# Luna_Board_Sheet.net
KiCad netlist of a schematic drawn in Altium Designer
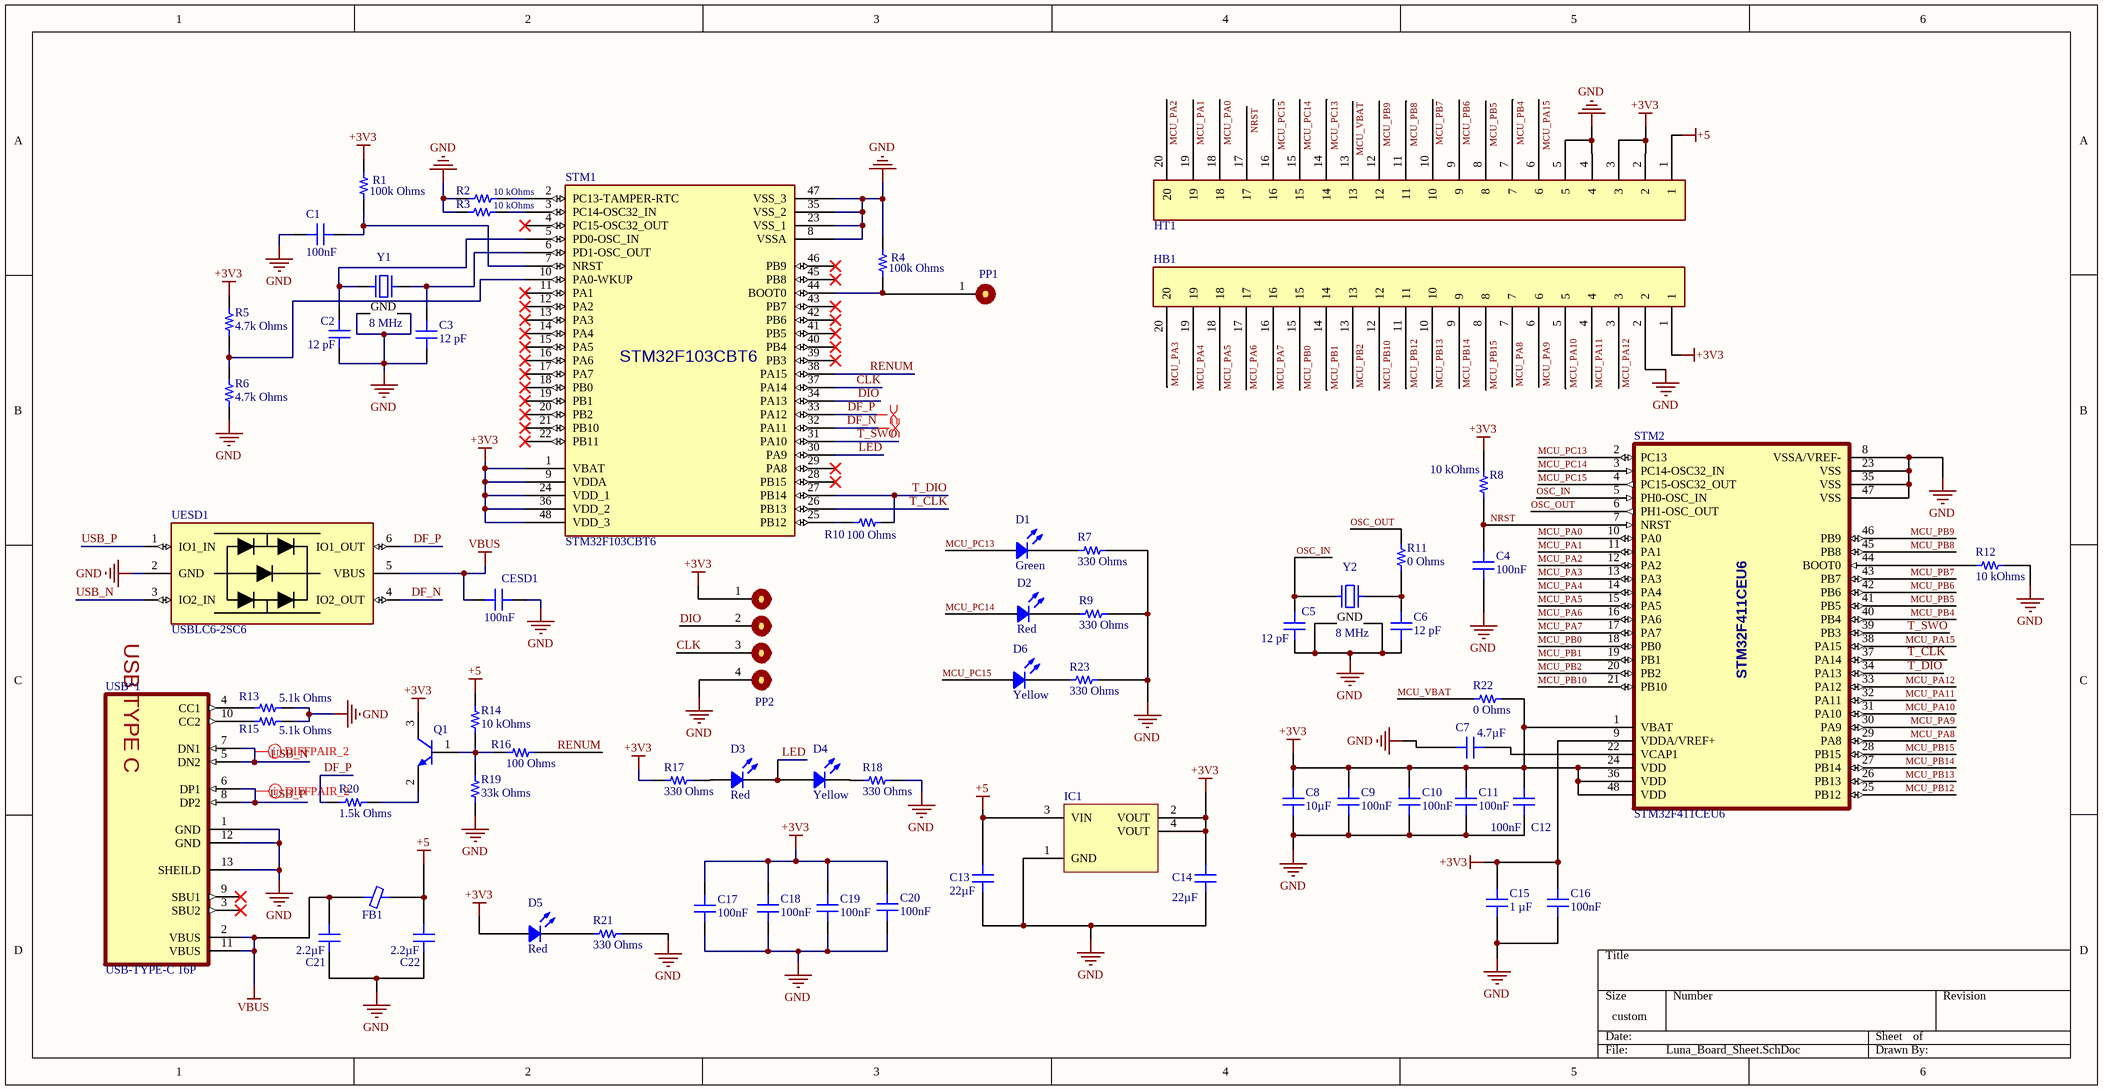
[diagram p0: Luna_Board_Sheet.SchDoc]

(export (version "E")
  (design (tool "Eeschema 10.0.6"))
  (components
    (comp (ref "C1")
      (value "100nF")
      (footprint "CAP 0603_1608")
      (description "CAP CER 0.1UF 100V X7R 0603")
      (fields
        (field (name "PART NUMBER") "06031C104KAT2A")
        (field (name "CAPACITANCE") "100nF")
        (field (name "MANUFACTURER") "AVX Corporation")
      )
      (libsource (lib "Celestial Altium Library - altium_library") (part "Capacitor"))
    )
    (comp (ref "C2")
      (value "12 pF")
      (footprint "CAP 0603_1608")
      (description "HIGH-Q MLCC (CF): 0603, 22 PF (1")
      (fields
        (field (name "PART NUMBER") "C06CF220F-9ZN-X0T")
        (field (name "CAPACITANCE") "12 pF")
        (field (name "MANUFACTURER") "Knowles Dielectric Labs")
      )
      (libsource (lib "Celestial Altium Library - altium_library") (part "Capacitor"))
    )
    (comp (ref "C3")
      (value "12 pF")
      (footprint "CAP 0603_1608")
      (description "HIGH-Q MLCC (CF): 0603, 22 PF (1")
      (fields
        (field (name "PART NUMBER") "C06CF220F-9ZN-X0T")
        (field (name "CAPACITANCE") "12 pF")
        (field (name "MANUFACTURER") "Knowles Dielectric Labs")
      )
      (libsource (lib "Celestial Altium Library - altium_library") (part "Capacitor"))
    )
    (comp (ref "C4")
      (value "100nF")
      (footprint "CAP 0603_1608")
      (description "CAP CER 0.1UF 100V X7R 0603")
      (fields
        (field (name "PART NUMBER") "06031C104KAT2A")
        (field (name "CAPACITANCE") "100nF")
        (field (name "MANUFACTURER") "AVX Corporation")
      )
      (libsource (lib "Celestial Altium Library - altium_library") (part "Capacitor"))
    )
    (comp (ref "C5")
      (value "12 pF")
      (footprint "CAP 0603_1608")
      (description "HIGH-Q MLCC (CF): 0603, 22 PF (1")
      (fields
        (field (name "PART NUMBER") "C06CF220F-9ZN-X0T")
        (field (name "CAPACITANCE") "12 pF")
        (field (name "MANUFACTURER") "Knowles Dielectric Labs")
      )
      (libsource (lib "Celestial Altium Library - altium_library") (part "Capacitor"))
    )
    (comp (ref "C6")
      (value "12 pF")
      (footprint "CAP 0603_1608")
      (description "HIGH-Q MLCC (CF): 0603, 22 PF (1")
      (fields
        (field (name "PART NUMBER") "C06CF220F-9ZN-X0T")
        (field (name "CAPACITANCE") "12 pF")
        (field (name "MANUFACTURER") "Knowles Dielectric Labs")
      )
      (libsource (lib "Celestial Altium Library - altium_library") (part "Capacitor"))
    )
    (comp (ref "C7")
      (value "4.7µF")
      (footprint "CAP 0603_1608")
      (description "CAP CER 4.7UF 10V Y5V 0603")
      (fields
        (field (name "PART NUMBER") "0603ZG475ZAT2A")
        (field (name "CAPACITANCE") "4.7µF")
        (field (name "MANUFACTURER") "AVX Corporation")
      )
      (libsource (lib "Celestial Altium Library - altium_library") (part "Capacitor"))
    )
    (comp (ref "C8")
      (value "10µF")
      (footprint "CAP 0603_1608")
      (description "CAP CER 10UF 10V X5R 0603")
      (fields
        (field (name "PART NUMBER") "0603ZD106KAT2A")
        (field (name "CAPACITANCE") "10µF")
        (field (name "MANUFACTURER") "AVX Corporation")
      )
      (libsource (lib "Celestial Altium Library - altium_library") (part "Capacitor"))
    )
    (comp (ref "C9")
      (value "100nF")
      (footprint "CAP 0603_1608")
      (description "CAP CER 0.1UF 100V X7R 0603")
      (fields
        (field (name "PART NUMBER") "06031C104KAT2A")
        (field (name "CAPACITANCE") "100nF")
        (field (name "MANUFACTURER") "AVX Corporation")
      )
      (libsource (lib "Celestial Altium Library - altium_library") (part "Capacitor"))
    )
    (comp (ref "C10")
      (value "100nF")
      (footprint "CAP 0603_1608")
      (description "CAP CER 0.1UF 100V X7R 0603")
      (fields
        (field (name "PART NUMBER") "06031C104KAT2A")
        (field (name "CAPACITANCE") "100nF")
        (field (name "MANUFACTURER") "AVX Corporation")
      )
      (libsource (lib "Celestial Altium Library - altium_library") (part "Capacitor"))
    )
    (comp (ref "C11")
      (value "100nF")
      (footprint "CAP 0603_1608")
      (description "CAP CER 0.1UF 100V X7R 0603")
      (fields
        (field (name "PART NUMBER") "06031C104KAT2A")
        (field (name "CAPACITANCE") "100nF")
        (field (name "MANUFACTURER") "AVX Corporation")
      )
      (libsource (lib "Celestial Altium Library - altium_library") (part "Capacitor"))
    )
    (comp (ref "C12")
      (value "100nF")
      (footprint "CAP 0603_1608")
      (description "CAP CER 0.1UF 100V X7R 0603")
      (fields
        (field (name "PART NUMBER") "06031C104KAT2A")
        (field (name "CAPACITANCE") "100nF")
        (field (name "MANUFACTURER") "AVX Corporation")
      )
      (libsource (lib "Celestial Altium Library - altium_library") (part "Capacitor"))
    )
    (comp (ref "C13")
      (value "22µF")
      (footprint "CAP 0805_2012")
      (description "CAP CER 22UF 10V X5R 0805")
      (fields
        (field (name "PART NUMBER") "0805ZD226MAT2A")
        (field (name "CAPACITANCE") "22µF")
        (field (name "MANUFACTURER") "AVX Corporation")
      )
      (libsource (lib "Celestial Altium Library - altium_library") (part "Capacitor"))
    )
    (comp (ref "C14")
      (value "22µF")
      (footprint "CAP 0805_2012")
      (description "CAP CER 22UF 10V X5R 0805")
      (fields
        (field (name "PART NUMBER") "0805ZD226MAT2A")
        (field (name "CAPACITANCE") "22µF")
        (field (name "MANUFACTURER") "AVX Corporation")
      )
      (libsource (lib "Celestial Altium Library - altium_library") (part "Capacitor"))
    )
    (comp (ref "C15")
      (value "1 µF")
      (footprint "CAP 0603_1608")
      (description "CAP SMT06031F16VDC")
      (fields
        (field (name "PART NUMBER") "NMC0603X7R105K16TRPF")
        (field (name "CAPACITANCE") "1 µF")
        (field (name "MANUFACTURER") "NIC Components Corp")
      )
      (libsource (lib "Celestial Altium Library - altium_library") (part "Capacitor"))
    )
    (comp (ref "C16")
      (value "100nF")
      (footprint "CAP 0603_1608")
      (description "CAP CER 0.1UF 100V X7R 0603")
      (fields
        (field (name "PART NUMBER") "06031C104KAT2A")
        (field (name "CAPACITANCE") "100nF")
        (field (name "MANUFACTURER") "AVX Corporation")
      )
      (libsource (lib "Celestial Altium Library - altium_library") (part "Capacitor"))
    )
    (comp (ref "C17")
      (value "100nF")
      (footprint "CAP 0603_1608")
      (description "CAP CER 0.1UF 100V X7R 0603")
      (fields
        (field (name "PART NUMBER") "06031C104KAT2A")
        (field (name "CAPACITANCE") "100nF")
        (field (name "MANUFACTURER") "AVX Corporation")
      )
      (libsource (lib "Celestial Altium Library - altium_library") (part "Capacitor"))
    )
    (comp (ref "C18")
      (value "100nF")
      (footprint "CAP 0603_1608")
      (description "CAP CER 0.1UF 100V X7R 0603")
      (fields
        (field (name "PART NUMBER") "06031C104KAT2A")
        (field (name "CAPACITANCE") "100nF")
        (field (name "MANUFACTURER") "AVX Corporation")
      )
      (libsource (lib "Celestial Altium Library - altium_library") (part "Capacitor"))
    )
    (comp (ref "C19")
      (value "100nF")
      (footprint "CAP 0603_1608")
      (description "CAP CER 0.1UF 100V X7R 0603")
      (fields
        (field (name "PART NUMBER") "06031C104KAT2A")
        (field (name "CAPACITANCE") "100nF")
        (field (name "MANUFACTURER") "AVX Corporation")
      )
      (libsource (lib "Celestial Altium Library - altium_library") (part "Capacitor"))
    )
    (comp (ref "C20")
      (value "100nF")
      (footprint "CAP 0603_1608")
      (description "CAP CER 0.1UF 100V X7R 0603")
      (fields
        (field (name "PART NUMBER") "06031C104KAT2A")
        (field (name "CAPACITANCE") "100nF")
        (field (name "MANUFACTURER") "AVX Corporation")
      )
      (libsource (lib "Celestial Altium Library - altium_library") (part "Capacitor"))
    )
    (comp (ref "C21")
      (value "2.2µF")
      (footprint "CAP 0603_1608")
      (description "CAP CER 0.1UF 100V X7R 0603")
      (fields
        (field (name "PART NUMBER") "06031C104KAT2A")
        (field (name "CAPACITANCE") "2.2µF")
        (field (name "MANUFACTURER") "AVX Corporation")
      )
      (libsource (lib "Celestial Altium Library - altium_library") (part "Capacitor"))
    )
    (comp (ref "C22")
      (value "2.2µF")
      (footprint "CAP 0603_1608")
      (description "CAP CER 0.1UF 100V X7R 0603")
      (fields
        (field (name "PART NUMBER") "06031C104KAT2A")
        (field (name "CAPACITANCE") "2.2µF")
        (field (name "MANUFACTURER") "AVX Corporation")
      )
      (libsource (lib "Celestial Altium Library - altium_library") (part "Capacitor"))
    )
    (comp (ref "CESD1")
      (value "100nF")
      (footprint "CAP 0603_1608")
      (description "CAP CER 0.1UF 100V X7R 0603")
      (fields
        (field (name "PART NUMBER") "06031C104KAT2A")
        (field (name "CAPACITANCE") "100nF")
        (field (name "MANUFACTURER") "AVX Corporation")
      )
      (libsource (lib "Celestial Altium Library - altium_library") (part "Capacitor"))
    )
    (comp (ref "D1")
      (value "Green")
      (footprint "LED 0805_2012 GREEN")
      (description "0805 LED RED 570NM DOMINANT, 565")
      (fields
        (field (name "PART NUMBER") "QBLP631-YG1-2943")
        (field (name "MANUFACTURER") "QT Brightek (QTB)")
      )
      (libsource (lib "Celestial Altium Library - altium_library") (part "LED"))
    )
    (comp (ref "D2")
      (value "Red")
      (footprint "LED 0805_2012 RED")
      (description "0805 LED RED 640NM DOMINANT, 660")
      (fields (field (name "PART NUMBER") "QBLP631-S3") (field (name "MANUFACTURER") "QT Brightek (QTB)"))
      (libsource (lib "Celestial Altium Library - altium_library") (part "LED"))
    )
    (comp (ref "D3")
      (value "Red")
      (footprint "LED 0805_2012 RED")
      (description "0805 LED RED 640NM DOMINANT, 660")
      (fields (field (name "PART NUMBER") "QBLP631-S3") (field (name "MANUFACTURER") "QT Brightek (QTB)"))
      (libsource (lib "Celestial Altium Library - altium_library") (part "LED"))
    )
    (comp (ref "D4")
      (value "Yellow")
      (footprint "LED 0805_2012 YELLOW")
      (description "LED YELLOW DIFFUSED 0805 SMD")
      (fields (field (name "PART NUMBER") "597-3222-407NF") (field (name "MANUFACTURER") "Dialight"))
      (libsource (lib "Celestial Altium Library - altium_library") (part "LED"))
    )
    (comp (ref "D5")
      (value "Red")
      (footprint "LED 0805_2012 RED")
      (description "0805 LED RED 640NM DOMINANT, 660")
      (fields (field (name "PART NUMBER") "QBLP631-S3") (field (name "MANUFACTURER") "QT Brightek (QTB)"))
      (libsource (lib "Celestial Altium Library - altium_library") (part "LED"))
    )
    (comp (ref "D6")
      (value "Yellow")
      (footprint "LED 0805_2012 YELLOW")
      (description "LED YELLOW DIFFUSED 0805 SMD")
      (fields (field (name "PART NUMBER") "597-3222-407NF") (field (name "MANUFACTURER") "Dialight"))
      (libsource (lib "Celestial Altium Library - altium_library") (part "LED"))
    )
    (comp (ref "FB1")
      (value "Ferrite Bead")
      (footprint "FER 0603_1608")
      (description "FERRITEBEAD SMD Z100MHZ=600OHM 7")
      (fields
        (field (name "PART NUMBER") "BLM18DN601SZ1D")
        (field (name "MANUFACTURER") "Murata Electronics")
      )
      (libsource (lib "Celestial Altium Library - altium_library") (part "Ferrite Chip"))
    )
    (comp (ref "HB1")
      (value "2.54mm_TH_1x20_pin_header")
      (footprint "2.54mm_TH_1x20_pin_header")
      (libsource (lib "ARAF_PERSONAL_INTEGRATED_LIBRARY") (part "2.54mm_TH_1x20_pin_header"))
    )
    (comp (ref "HT1")
      (value "2.54mm_TH_1x20_pin_header")
      (footprint "2.54mm_TH_1x20_pin_header")
      (libsource (lib "") (part "2.54mm_TH_1x20_pin_header_1"))
    )
    (comp (ref "IC1")
      (value "AMS1117-3.3")
      (footprint "ST SOT-223")
      (description "IC REG LINEAR 3.3V 1.2A SOT223")
      (fields (field (name "PART NUMBER") "LDL1117S33R") (field (name "MANUFACTURER") "STMicroelectronics"))
      (libsource (lib "Celestial Altium Library - altium_library") (part "ST LDL1117"))
    )
    (comp (ref "PP1")
      (value "pin_pad_1")
      (footprint "pinpad_1")
      (libsource (lib "ARAF_PERSONAL_INTEGRATED_LIBRARY") (part "pin_pad_1"))
    )
    (comp (ref "PP2")
      (value "pin_pad_4")
      (footprint "pinpad_4")
      (libsource (lib "ARAF_PERSONAL_INTEGRATED_LIBRARY") (part "pin_pad_4"))
    )
    (comp (ref "Q1")
      (value "500mA NPN BJT")
      (footprint "DIODES SOT-23-3")
      (description "TRANS NPN 60V 1A SOT23-3")
      (fields (field (name "PART NUMBER") "DNLS160-7") (field (name "MANUFACTURER") "Diodes Incorporated"))
      (libsource (lib "Celestial Altium Library - altium_library") (part "DIODES INC NPN SOT-23-3"))
    )
    (comp (ref "R1")
      (value "100k Ohms")
      (footprint "RES 0603_1608")
      (description "RES 100K OHM 0.1% 1/16W 0603")
      (fields
        (field (name "PART NUMBER") "RNCS0603BKE10K0")
        (field (name "MANUFACTURER") "Stackpole Electronics Inc")
      )
      (libsource (lib "Celestial Altium Library - altium_library") (part "Resistor"))
    )
    (comp (ref "R2")
      (value "10 kOhms")
      (footprint "RES 0603_1608")
      (description "RES 10K OHM 0.1% 1/16W 0603")
      (fields
        (field (name "PART NUMBER") "RNCS0603BKE10K0")
        (field (name "MANUFACTURER") "Stackpole Electronics Inc")
      )
      (libsource (lib "Celestial Altium Library - altium_library") (part "Resistor"))
    )
    (comp (ref "R3")
      (value "10 kOhms")
      (footprint "RES 0603_1608")
      (description "RES 10K OHM 0.1% 1/16W 0603")
      (fields
        (field (name "PART NUMBER") "RNCS0603BKE10K0")
        (field (name "MANUFACTURER") "Stackpole Electronics Inc")
      )
      (libsource (lib "Celestial Altium Library - altium_library") (part "Resistor"))
    )
    (comp (ref "R4")
      (value "100k Ohms")
      (footprint "RES 0603_1608")
      (description "RES 100K OHM 0.1% 1/16W 0603")
      (fields
        (field (name "PART NUMBER") "RNCS0603BKE10K0")
        (field (name "MANUFACTURER") "Stackpole Electronics Inc")
      )
      (libsource (lib "Celestial Altium Library - altium_library") (part "Resistor"))
    )
    (comp (ref "R5")
      (value "4.7k Ohms")
      (footprint "RES 0603_1608")
      (description "RES 4.7K OHM 0.1% 1/16W 0603")
      (fields
        (field (name "PART NUMBER") "RNCS0603BKE10K0")
        (field (name "MANUFACTURER") "Stackpole Electronics Inc")
      )
      (libsource (lib "Celestial Altium Library - altium_library") (part "Resistor"))
    )
    (comp (ref "R6")
      (value "4.7k Ohms")
      (footprint "RES 0603_1608")
      (description "RES 4.7k OHM 0.1% 1/16W 0603")
      (fields
        (field (name "PART NUMBER") "RNCS0603BKE10K0")
        (field (name "MANUFACTURER") "Stackpole Electronics Inc")
      )
      (libsource (lib "Celestial Altium Library - altium_library") (part "Resistor"))
    )
    (comp (ref "R7")
      (value "330 Ohms")
      (footprint "RES 0603_1608")
      (description "RES 10K OHM 0.1% 1/16W 0603")
      (fields
        (field (name "PART NUMBER") "RNCS0603BKE10K0")
        (field (name "MANUFACTURER") "Stackpole Electronics Inc")
      )
      (libsource (lib "Celestial Altium Library - altium_library") (part "Resistor"))
    )
    (comp (ref "R8")
      (value "10 kOhms")
      (footprint "RES 0603_1608")
      (description "RES 10K OHM 0.1% 1/16W 0603")
      (fields
        (field (name "PART NUMBER") "RNCS0603BKE10K0")
        (field (name "MANUFACTURER") "Stackpole Electronics Inc")
      )
      (libsource (lib "Celestial Altium Library - altium_library") (part "Resistor"))
    )
    (comp (ref "R9")
      (value "330 Ohms")
      (footprint "RES 0603_1608")
      (description "RES 10K OHM 0.1% 1/16W 0603")
      (fields
        (field (name "PART NUMBER") "RNCS0603BKE10K0")
        (field (name "MANUFACTURER") "Stackpole Electronics Inc")
      )
      (libsource (lib "Celestial Altium Library - altium_library") (part "Resistor"))
    )
    (comp (ref "R10")
      (value "100 Ohms")
      (footprint "RES 0603_1608")
      (description "RES 100 OHM 0.1% 1/16W 0603")
      (fields
        (field (name "PART NUMBER") "RNCS0603BKE10K0")
        (field (name "MANUFACTURER") "Stackpole Electronics Inc")
      )
      (libsource (lib "Celestial Altium Library - altium_library") (part "Resistor"))
    )
    (comp (ref "R11")
      (value "0 Ohms")
      (footprint "RES 0603_1608")
      (description "RES 0 OHM JUMPER 0603")
      (fields
        (field (name "PART NUMBER") "TLRZ1JTTD")
        (field (name "MANUFACTURER") "KOA Speer Electronics, Inc.")
      )
      (libsource (lib "Celestial Altium Library - altium_library") (part "Resistor"))
    )
    (comp (ref "R12")
      (value "10 kOhms")
      (footprint "RES 0603_1608")
      (description "RES 10K OHM 0.1% 1/16W 0603")
      (fields
        (field (name "PART NUMBER") "RNCS0603BKE10K0")
        (field (name "MANUFACTURER") "Stackpole Electronics Inc")
      )
      (libsource (lib "Celestial Altium Library - altium_library") (part "Resistor"))
    )
    (comp (ref "R13")
      (value "5.1k Ohms")
      (footprint "RES 0603_1608")
      (description "RES 10K OHM 0.1% 1/16W 0603")
      (fields
        (field (name "PART NUMBER") "RNCS0603BKE10K0")
        (field (name "MANUFACTURER") "Stackpole Electronics Inc")
      )
      (libsource (lib "Celestial Altium Library - altium_library") (part "Resistor"))
    )
    (comp (ref "R14")
      (value "10 kOhms")
      (footprint "RES 0603_1608")
      (description "RES 10K OHM 0.1% 1/16W 0603")
      (fields
        (field (name "PART NUMBER") "RNCS0603BKE10K0")
        (field (name "MANUFACTURER") "Stackpole Electronics Inc")
      )
      (libsource (lib "Celestial Altium Library - altium_library") (part "Resistor"))
    )
    (comp (ref "R15")
      (value "5.1k Ohms")
      (footprint "RES 0603_1608")
      (description "RES 10K OHM 0.1% 1/16W 0603")
      (fields
        (field (name "PART NUMBER") "RNCS0603BKE10K0")
        (field (name "MANUFACTURER") "Stackpole Electronics Inc")
      )
      (libsource (lib "Celestial Altium Library - altium_library") (part "Resistor"))
    )
    (comp (ref "R16")
      (value "100 Ohms")
      (footprint "RES 0603_1608")
      (description "RES 10K OHM 0.1% 1/16W 0603")
      (fields
        (field (name "PART NUMBER") "RNCS0603BKE10K0")
        (field (name "MANUFACTURER") "Stackpole Electronics Inc")
      )
      (libsource (lib "Celestial Altium Library - altium_library") (part "Resistor"))
    )
    (comp (ref "R17")
      (value "330 Ohms")
      (footprint "RES 0603_1608")
      (description "RES 10K OHM 0.1% 1/16W 0603")
      (fields
        (field (name "PART NUMBER") "RNCS0603BKE10K0")
        (field (name "MANUFACTURER") "Stackpole Electronics Inc")
      )
      (libsource (lib "Celestial Altium Library - altium_library") (part "Resistor"))
    )
    (comp (ref "R18")
      (value "330 Ohms")
      (footprint "RES 0603_1608")
      (description "RES 10K OHM 0.1% 1/16W 0603")
      (fields
        (field (name "PART NUMBER") "RNCS0603BKE10K0")
        (field (name "MANUFACTURER") "Stackpole Electronics Inc")
      )
      (libsource (lib "Celestial Altium Library - altium_library") (part "Resistor"))
    )
    (comp (ref "R19")
      (value "33k Ohms")
      (footprint "RES 0603_1608")
      (description "RES 10K OHM 0.1% 1/16W 0603")
      (fields
        (field (name "PART NUMBER") "RNCS0603BKE10K0")
        (field (name "MANUFACTURER") "Stackpole Electronics Inc")
      )
      (libsource (lib "Celestial Altium Library - altium_library") (part "Resistor"))
    )
    (comp (ref "R20")
      (value "1.5k Ohms")
      (footprint "RES 0603_1608")
      (description "RES 10K OHM 0.1% 1/16W 0603")
      (fields
        (field (name "PART NUMBER") "RNCS0603BKE10K0")
        (field (name "MANUFACTURER") "Stackpole Electronics Inc")
      )
      (libsource (lib "Celestial Altium Library - altium_library") (part "Resistor"))
    )
    (comp (ref "R21")
      (value "330 Ohms")
      (footprint "RES 0603_1608")
      (description "RES 10K OHM 0.1% 1/16W 0603")
      (fields
        (field (name "PART NUMBER") "RNCS0603BKE10K0")
        (field (name "MANUFACTURER") "Stackpole Electronics Inc")
      )
      (libsource (lib "Celestial Altium Library - altium_library") (part "Resistor"))
    )
    (comp (ref "R22")
      (value "0 Ohms")
      (footprint "RES 0603_1608")
      (description "RES 0 OHM JUMPER 0603")
      (fields
        (field (name "PART NUMBER") "TLRZ1JTTD")
        (field (name "MANUFACTURER") "KOA Speer Electronics, Inc.")
      )
      (libsource (lib "Celestial Altium Library - altium_library") (part "Resistor"))
    )
    (comp (ref "R23")
      (value "330 Ohms")
      (footprint "RES 0603_1608")
      (description "RES 10K OHM 0.1% 1/16W 0603")
      (fields
        (field (name "PART NUMBER") "RNCS0603BKE10K0")
        (field (name "MANUFACTURER") "Stackpole Electronics Inc")
      )
      (libsource (lib "Celestial Altium Library - altium_library") (part "Resistor"))
    )
    (comp (ref "STM1")
      (value "STM32F103CBT6")
      (footprint "STM32F103CBT6_FOOTPRINT")
      (description "128KB 2V~3.6V ARM-M3 20KB 72MHz FLASH 37 LQFP-48(7x7) Microcontrollers (MCU/MPU/SOC) ROHS")
      (fields (field (name "JLCPCB PART #") "C8304"))
      (libsource (lib "ARAF_PERSONAL_INTEGRATED_LIBRARY") (part "STM32F103CBT6"))
    )
    (comp (ref "STM2")
      (value "STM32F411CEU6")
      (footprint "STM32F411CEU6_Footprint")
      (libsource (lib "STM32F_Series_SCH_Library_ARAF") (part "STM32F411CEU6"))
    )
    (comp (ref "UESD1")
      (value "USBLC6-2SC6")
      (footprint "USBLC6-2SC6_Footprint")
      (fields (field (name "JLCPCB PART #") "C7519"))
      (libsource (lib "ESD_Protection_Components_Series_SCH_Library_ARAF") (part "USBLC6-2"))
    )
    (comp (ref "USB*1")
      (value "USB-TYPE-C 16P")
      (footprint "USB TYPE-C 24P SMD")
      (fields (field (name "LCSC PART") "C2765186"))
      (libsource (lib "USB_Connector_Series_SCH_Library_ARAF") (part "USB TYPE-C 24P SMD"))
    )
    (comp (ref "Y1")
      (value "8 MHz")
      (footprint "EPSON TSX-3225")
      (fields (field (name "PART NUMBER") "TSX-3225 16.0000MF10U-B0") (field (name "MANUFACTURER") "EPSON"))
      (libsource (lib "Celestial Altium Library - altium_library") (part "Epson Crystal TSX-3225"))
    )
    (comp (ref "Y2")
      (value "8 MHz")
      (footprint "EPSON TSX-3225")
      (description "CRYSTAL 16.0000MHZ 16PF SMD")
      (fields (field (name "PART NUMBER") "TSX-3225 16.0000MF10U-B0") (field (name "MANUFACTURER") "EPSON"))
      (libsource (lib "Celestial Altium Library - altium_library") (part "Epson Crystal TSX-3225"))
    )
  )
  (nets
    (net (code "1") (name "+3V3") (class "Default")
      (node (ref "C10") (pin "2") (pinfunction "2_2") (pintype "passive"))
      (node (ref "C11") (pin "2") (pinfunction "2_2") (pintype "passive"))
      (node (ref "C12") (pin "2") (pinfunction "2_2") (pintype "passive"))
      (node (ref "C14") (pin "2") (pinfunction "2_2") (pintype "passive"))
      (node (ref "C15") (pin "2") (pinfunction "2_2") (pintype "passive"))
      (node (ref "C16") (pin "2") (pinfunction "2_2") (pintype "passive"))
      (node (ref "C17") (pin "2") (pinfunction "2_2") (pintype "passive"))
      (node (ref "C18") (pin "2") (pinfunction "2_2") (pintype "passive"))
      (node (ref "C19") (pin "2") (pinfunction "2_2") (pintype "passive"))
      (node (ref "C20") (pin "2") (pinfunction "2_2") (pintype "passive"))
      (node (ref "C8") (pin "2") (pinfunction "2_2") (pintype "passive"))
      (node (ref "C9") (pin "2") (pinfunction "2_2") (pintype "passive"))
      (node (ref "D5") (pin "1") (pinfunction "1_1") (pintype "passive"))
      (node (ref "HB1") (pin "1") (pinfunction "1_1") (pintype "passive"))
      (node (ref "HT1") (pin "2") (pinfunction "2_2") (pintype "passive"))
      (node (ref "HT1") (pin "3") (pinfunction "3_3") (pintype "passive"))
      (node (ref "IC1") (pin "2") (pinfunction "VOUT_2") (pintype "passive"))
      (node (ref "IC1") (pin "4") (pinfunction "VOUT_4") (pintype "passive"))
      (node (ref "PP2") (pin "1") (pinfunction "1_1") (pintype "passive"))
      (node (ref "Q1") (pin "3") (pinfunction "C_3") (pintype "passive"))
      (node (ref "R1") (pin "1") (pinfunction "1_1") (pintype "passive"))
      (node (ref "R17") (pin "1") (pinfunction "1_1") (pintype "passive"))
      (node (ref "R22") (pin "1") (pinfunction "1_1") (pintype "passive"))
      (node (ref "R5") (pin "2") (pinfunction "2_2") (pintype "passive"))
      (node (ref "R8") (pin "1") (pinfunction "1_1") (pintype "passive"))
      (node (ref "STM1") (pin "1") (pinfunction "VBAT_1") (pintype "power_in"))
      (node (ref "STM1") (pin "24") (pinfunction "VDD_1_24") (pintype "power_in"))
      (node (ref "STM1") (pin "36") (pinfunction "VDD_2_36") (pintype "power_in"))
      (node (ref "STM1") (pin "48") (pinfunction "VDD_3_48") (pintype "power_in"))
      (node (ref "STM1") (pin "9") (pinfunction "VDDA_9") (pintype "power_in"))
      (node (ref "STM2") (pin "1") (pinfunction "VBAT_1") (pintype "power_in"))
      (node (ref "STM2") (pin "24") (pinfunction "VDD_24") (pintype "power_in"))
      (node (ref "STM2") (pin "36") (pinfunction "VDD_36") (pintype "power_in"))
      (node (ref "STM2") (pin "48") (pinfunction "VDD_48") (pintype "power_in"))
      (node (ref "STM2") (pin "9") (pinfunction "VDDA/VREF+_9") (pintype "power_in"))
    )
    (net (code "2") (name "+5") (class "Default")
      (node (ref "C13") (pin "2") (pinfunction "2_2") (pintype "passive"))
      (node (ref "C22") (pin "1") (pinfunction "1_1") (pintype "passive"))
      (node (ref "FB1") (pin "1") (pinfunction "1_1") (pintype "passive"))
      (node (ref "HT1") (pin "1") (pinfunction "1_1") (pintype "passive"))
      (node (ref "IC1") (pin "3") (pinfunction "VIN_3") (pintype "passive"))
      (node (ref "R14") (pin "2") (pinfunction "2_2") (pintype "passive"))
    )
    (net (code "3") (name "/CLK") (class "Default")
      (node (ref "PP2") (pin "3") (pinfunction "3_3") (pintype "passive"))
      (node (ref "STM1") (pin "37") (pinfunction "PA14_37") (pintype "bidirectional"))
    )
    (net (code "4") (name "/DF_N") (class "Default")
      (node (ref "STM1") (pin "32") (pinfunction "PA11_32") (pintype "bidirectional"))
      (node (ref "UESD1") (pin "4") (pinfunction "IO2_OUT_4") (pintype "bidirectional"))
    )
    (net (code "5") (name "/DF_P") (class "Default")
      (node (ref "R20") (pin "1") (pinfunction "1_1") (pintype "passive"))
      (node (ref "STM1") (pin "33") (pinfunction "PA12_33") (pintype "bidirectional"))
      (node (ref "UESD1") (pin "6") (pinfunction "IO1_OUT_6") (pintype "bidirectional"))
    )
    (net (code "6") (name "/DIO") (class "Default")
      (node (ref "PP2") (pin "2") (pinfunction "2_2") (pintype "passive"))
      (node (ref "STM1") (pin "34") (pinfunction "PA13_34") (pintype "bidirectional"))
    )
    (net (code "7") (name "/LED") (class "Default")
      (node (ref "D3") (pin "2") (pinfunction "2_2") (pintype "passive"))
      (node (ref "D4") (pin "1") (pinfunction "1_1") (pintype "passive"))
      (node (ref "STM1") (pin "30") (pinfunction "PA9_30") (pintype "bidirectional"))
    )
    (net (code "8") (name "/MCU_PA0") (class "Default")
      (node (ref "HT1") (pin "18") (pinfunction "18_18") (pintype "passive"))
      (node (ref "STM2") (pin "10") (pinfunction "PA0_10") (pintype "bidirectional"))
    )
    (net (code "9") (name "/MCU_PA1") (class "Default")
      (node (ref "HT1") (pin "19") (pinfunction "19_19") (pintype "passive"))
      (node (ref "STM2") (pin "11") (pinfunction "PA1_11") (pintype "bidirectional"))
    )
    (net (code "10") (name "/MCU_PA2") (class "Default")
      (node (ref "HT1") (pin "20") (pinfunction "20_20") (pintype "passive"))
      (node (ref "STM2") (pin "12") (pinfunction "PA2_12") (pintype "bidirectional"))
    )
    (net (code "11") (name "/MCU_PA3") (class "Default")
      (node (ref "HB1") (pin "20") (pinfunction "20_20") (pintype "passive"))
      (node (ref "STM2") (pin "13") (pinfunction "PA3_13") (pintype "bidirectional"))
    )
    (net (code "12") (name "/MCU_PA4") (class "Default")
      (node (ref "HB1") (pin "19") (pinfunction "19_19") (pintype "passive"))
      (node (ref "STM2") (pin "14") (pinfunction "PA4_14") (pintype "bidirectional"))
    )
    (net (code "13") (name "/MCU_PA5") (class "Default")
      (node (ref "HB1") (pin "18") (pinfunction "18_18") (pintype "passive"))
      (node (ref "STM2") (pin "15") (pinfunction "PA5_15") (pintype "bidirectional"))
    )
    (net (code "14") (name "/MCU_PA6") (class "Default")
      (node (ref "HB1") (pin "17") (pinfunction "17_17") (pintype "passive"))
      (node (ref "STM2") (pin "16") (pinfunction "PA6_16") (pintype "bidirectional"))
    )
    (net (code "15") (name "/MCU_PA7") (class "Default")
      (node (ref "HB1") (pin "16") (pinfunction "16_16") (pintype "passive"))
      (node (ref "STM2") (pin "17") (pinfunction "PA7_17") (pintype "bidirectional"))
    )
    (net (code "16") (name "/MCU_PA8") (class "Default")
      (node (ref "HB1") (pin "7") (pinfunction "7_7") (pintype "passive"))
      (node (ref "STM2") (pin "29") (pinfunction "PA8_29") (pintype "bidirectional"))
    )
    (net (code "17") (name "/MCU_PA9") (class "Default")
      (node (ref "HB1") (pin "6") (pinfunction "6_6") (pintype "passive"))
      (node (ref "STM2") (pin "30") (pinfunction "PA9_30") (pintype "bidirectional"))
    )
    (net (code "18") (name "/MCU_PA10") (class "Default")
      (node (ref "HB1") (pin "5") (pinfunction "5_5") (pintype "passive"))
      (node (ref "STM2") (pin "31") (pinfunction "PA10_31") (pintype "bidirectional"))
    )
    (net (code "19") (name "/MCU_PA11") (class "Default")
      (node (ref "HB1") (pin "4") (pinfunction "4_4") (pintype "passive"))
      (node (ref "STM2") (pin "32") (pinfunction "PA11_32") (pintype "bidirectional"))
    )
    (net (code "20") (name "/MCU_PA12") (class "Default")
      (node (ref "HB1") (pin "3") (pinfunction "3_3") (pintype "passive"))
      (node (ref "STM2") (pin "33") (pinfunction "PA12_33") (pintype "bidirectional"))
    )
    (net (code "21") (name "/MCU_PA15") (class "Default")
      (node (ref "HT1") (pin "6") (pinfunction "6_6") (pintype "passive"))
      (node (ref "STM2") (pin "38") (pinfunction "PA15_38") (pintype "bidirectional"))
    )
    (net (code "22") (name "/MCU_PB0") (class "Default")
      (node (ref "HB1") (pin "15") (pinfunction "15_15") (pintype "passive"))
      (node (ref "STM2") (pin "18") (pinfunction "PB0_18") (pintype "bidirectional"))
    )
    (net (code "23") (name "/MCU_PB1") (class "Default")
      (node (ref "HB1") (pin "14") (pinfunction "14_14") (pintype "passive"))
      (node (ref "STM2") (pin "19") (pinfunction "PB1_19") (pintype "bidirectional"))
    )
    (net (code "24") (name "/MCU_PB2") (class "Default")
      (node (ref "HB1") (pin "13") (pinfunction "13_13") (pintype "passive"))
      (node (ref "STM2") (pin "20") (pinfunction "PB2_20") (pintype "bidirectional"))
    )
    (net (code "25") (name "/MCU_PB4") (class "Default")
      (node (ref "HT1") (pin "7") (pinfunction "7_7") (pintype "passive"))
      (node (ref "STM2") (pin "40") (pinfunction "PB4_40") (pintype "bidirectional"))
    )
    (net (code "26") (name "/MCU_PB5") (class "Default")
      (node (ref "HT1") (pin "8") (pinfunction "8_8") (pintype "passive"))
      (node (ref "STM2") (pin "41") (pinfunction "PB5_41") (pintype "bidirectional"))
    )
    (net (code "27") (name "/MCU_PB6") (class "Default")
      (node (ref "HT1") (pin "9") (pinfunction "9_9") (pintype "passive"))
      (node (ref "STM2") (pin "42") (pinfunction "PB6_42") (pintype "bidirectional"))
    )
    (net (code "28") (name "/MCU_PB7") (class "Default")
      (node (ref "HT1") (pin "10") (pinfunction "10_10") (pintype "passive"))
      (node (ref "STM2") (pin "43") (pinfunction "PB7_43") (pintype "bidirectional"))
    )
    (net (code "29") (name "/MCU_PB8") (class "Default")
      (node (ref "HT1") (pin "11") (pinfunction "11_11") (pintype "passive"))
      (node (ref "STM2") (pin "45") (pinfunction "PB8_45") (pintype "bidirectional"))
    )
    (net (code "30") (name "/MCU_PB9") (class "Default")
      (node (ref "HT1") (pin "12") (pinfunction "12_12") (pintype "passive"))
      (node (ref "STM2") (pin "46") (pinfunction "PB9_46") (pintype "bidirectional"))
    )
    (net (code "31") (name "/MCU_PB10") (class "Default")
      (node (ref "HB1") (pin "12") (pinfunction "12_12") (pintype "passive"))
      (node (ref "STM2") (pin "21") (pinfunction "PB10_21") (pintype "bidirectional"))
    )
    (net (code "32") (name "/MCU_PB12") (class "Default")
      (node (ref "HB1") (pin "11") (pinfunction "11_11") (pintype "passive"))
      (node (ref "STM2") (pin "25") (pinfunction "PB12_25") (pintype "bidirectional"))
    )
    (net (code "33") (name "/MCU_PB13") (class "Default")
      (node (ref "HB1") (pin "10") (pinfunction "10_10") (pintype "passive"))
      (node (ref "STM2") (pin "26") (pinfunction "PB13_26") (pintype "bidirectional"))
    )
    (net (code "34") (name "/MCU_PB14") (class "Default")
      (node (ref "HB1") (pin "9") (pinfunction "9_9") (pintype "passive"))
      (node (ref "STM2") (pin "27") (pinfunction "PB14_27") (pintype "bidirectional"))
    )
    (net (code "35") (name "/MCU_PB15") (class "Default")
      (node (ref "HB1") (pin "8") (pinfunction "8_8") (pintype "passive"))
      (node (ref "STM2") (pin "28") (pinfunction "PB15_28") (pintype "bidirectional"))
    )
    (net (code "36") (name "/MCU_PC13") (class "Default")
      (node (ref "D1") (pin "1") (pinfunction "1_1") (pintype "passive"))
      (node (ref "HT1") (pin "14") (pinfunction "14_14") (pintype "passive"))
      (node (ref "STM2") (pin "2") (pinfunction "PC13_2") (pintype "bidirectional"))
    )
    (net (code "37") (name "/MCU_PC14") (class "Default")
      (node (ref "D2") (pin "1") (pinfunction "1_1") (pintype "passive"))
      (node (ref "HT1") (pin "15") (pinfunction "15_15") (pintype "passive"))
      (node (ref "STM2") (pin "3") (pinfunction "PC14-OSC32_IN_3") (pintype "input"))
    )
    (net (code "38") (name "/MCU_PC15") (class "Default")
      (node (ref "D6") (pin "1") (pinfunction "1_1") (pintype "passive"))
      (node (ref "HT1") (pin "16") (pinfunction "16_16") (pintype "passive"))
      (node (ref "STM2") (pin "4") (pinfunction "PC15-OSC32_OUT_4") (pintype "output"))
    )
    (net (code "39") (name "/MCU_VBAT") (class "Default")
      (node (ref "HT1") (pin "13") (pinfunction "13_13") (pintype "passive"))
      (node (ref "R22") (pin "2") (pinfunction "2_2") (pintype "passive"))
    )
    (net (code "40") (name "/NRST") (class "Default")
      (node (ref "C4") (pin "2") (pinfunction "2_2") (pintype "passive"))
      (node (ref "HT1") (pin "17") (pinfunction "17_17") (pintype "passive"))
      (node (ref "R8") (pin "2") (pinfunction "2_2") (pintype "passive"))
      (node (ref "STM2") (pin "7") (pinfunction "NRST_7") (pintype "input"))
    )
    (net (code "41") (name "/OSC_IN") (class "Default")
      (node (ref "C5") (pin "2") (pinfunction "2_2") (pintype "passive"))
      (node (ref "STM2") (pin "5") (pinfunction "PH0-OSC_IN_5") (pintype "input"))
      (node (ref "Y2") (pin "1") (pinfunction "1_1") (pintype "passive"))
    )
    (net (code "42") (name "/OSC_OUT") (class "Default")
      (node (ref "R11") (pin "2") (pinfunction "2_2") (pintype "passive"))
      (node (ref "STM2") (pin "6") (pinfunction "PH1-OSC_OUT_6") (pintype "output"))
    )
    (net (code "43") (name "/RENUM") (class "Default")
      (node (ref "R16") (pin "2") (pinfunction "2_2") (pintype "passive"))
      (node (ref "STM1") (pin "38") (pinfunction "PA15_38") (pintype "bidirectional"))
    )
    (net (code "44") (name "/T_CLK") (class "Default")
      (node (ref "STM1") (pin "26") (pinfunction "PB13_26") (pintype "bidirectional"))
      (node (ref "STM2") (pin "37") (pinfunction "PA14_37") (pintype "bidirectional"))
    )
    (net (code "45") (name "/T_DIO") (class "Default")
      (node (ref "R10") (pin "2") (pinfunction "2_2") (pintype "passive"))
      (node (ref "STM1") (pin "27") (pinfunction "PB14_27") (pintype "bidirectional"))
      (node (ref "STM2") (pin "34") (pinfunction "PA13_34") (pintype "bidirectional"))
    )
    (net (code "46") (name "/T_SWO") (class "Default")
      (node (ref "STM1") (pin "31") (pinfunction "PA10_31") (pintype "bidirectional"))
      (node (ref "STM2") (pin "39") (pinfunction "PB3_39") (pintype "bidirectional"))
    )
    (net (code "47") (name "/USB_N") (class "Default")
      (node (ref "UESD1") (pin "3") (pinfunction "IO2_IN_3") (pintype "bidirectional"))
      (node (ref "USB*1") (pin "5") (pinfunction "DN2_5") (pintype "input"))
      (node (ref "USB*1") (pin "7") (pinfunction "DN1_7") (pintype "input"))
    )
    (net (code "48") (name "/USB_P") (class "Default")
      (node (ref "UESD1") (pin "1") (pinfunction "IO1_IN_1") (pintype "bidirectional"))
      (node (ref "USB*1") (pin "6") (pinfunction "DP1_6") (pintype "input"))
      (node (ref "USB*1") (pin "8") (pinfunction "DP2_8") (pintype "input"))
    )
    (net (code "49") (name "GND") (class "Default")
      (node (ref "C1") (pin "1") (pinfunction "1_1") (pintype "passive"))
      (node (ref "C10") (pin "1") (pinfunction "1_1") (pintype "passive"))
      (node (ref "C11") (pin "1") (pinfunction "1_1") (pintype "passive"))
      (node (ref "C12") (pin "1") (pinfunction "1_1") (pintype "passive"))
      (node (ref "C13") (pin "1") (pinfunction "1_1") (pintype "passive"))
      (node (ref "C14") (pin "1") (pinfunction "1_1") (pintype "passive"))
      (node (ref "C15") (pin "1") (pinfunction "1_1") (pintype "passive"))
      (node (ref "C16") (pin "1") (pinfunction "1_1") (pintype "passive"))
      (node (ref "C17") (pin "1") (pinfunction "1_1") (pintype "passive"))
      (node (ref "C18") (pin "1") (pinfunction "1_1") (pintype "passive"))
      (node (ref "C19") (pin "1") (pinfunction "1_1") (pintype "passive"))
      (node (ref "C2") (pin "1") (pinfunction "1_1") (pintype "passive"))
      (node (ref "C20") (pin "1") (pinfunction "1_1") (pintype "passive"))
      (node (ref "C21") (pin "2") (pinfunction "2_2") (pintype "passive"))
      (node (ref "C22") (pin "2") (pinfunction "2_2") (pintype "passive"))
      (node (ref "C3") (pin "1") (pinfunction "1_1") (pintype "passive"))
      (node (ref "C4") (pin "1") (pinfunction "1_1") (pintype "passive"))
      (node (ref "C5") (pin "1") (pinfunction "1_1") (pintype "passive"))
      (node (ref "C6") (pin "1") (pinfunction "1_1") (pintype "passive"))
      (node (ref "C7") (pin "2") (pinfunction "2_2") (pintype "passive"))
      (node (ref "C8") (pin "1") (pinfunction "1_1") (pintype "passive"))
      (node (ref "C9") (pin "1") (pinfunction "1_1") (pintype "passive"))
      (node (ref "CESD1") (pin "1") (pinfunction "1_1") (pintype "passive"))
      (node (ref "HB1") (pin "2") (pinfunction "2_2") (pintype "passive"))
      (node (ref "HT1") (pin "4") (pinfunction "4_4") (pintype "passive"))
      (node (ref "HT1") (pin "5") (pinfunction "5_5") (pintype "passive"))
      (node (ref "IC1") (pin "1") (pinfunction "GND_1") (pintype "passive"))
      (node (ref "PP2") (pin "4") (pinfunction "4_4") (pintype "passive"))
      (node (ref "R12") (pin "1") (pinfunction "1_1") (pintype "passive"))
      (node (ref "R13") (pin "2") (pinfunction "2_2") (pintype "passive"))
      (node (ref "R15") (pin "2") (pinfunction "2_2") (pintype "passive"))
      (node (ref "R18") (pin "2") (pinfunction "2_2") (pintype "passive"))
      (node (ref "R19") (pin "1") (pinfunction "1_1") (pintype "passive"))
      (node (ref "R2") (pin "1") (pinfunction "1_1") (pintype "passive"))
      (node (ref "R21") (pin "2") (pinfunction "2_2") (pintype "passive"))
      (node (ref "R23") (pin "2") (pinfunction "2_2") (pintype "passive"))
      (node (ref "R3") (pin "1") (pinfunction "1_1") (pintype "passive"))
      (node (ref "R4") (pin "1") (pinfunction "1_1") (pintype "passive"))
      (node (ref "R6") (pin "1") (pinfunction "1_1") (pintype "passive"))
      (node (ref "R7") (pin "2") (pinfunction "2_2") (pintype "passive"))
      (node (ref "R9") (pin "2") (pinfunction "2_2") (pintype "passive"))
      (node (ref "STM1") (pin "23") (pinfunction "VSS_1_23") (pintype "power_in"))
      (node (ref "STM1") (pin "35") (pinfunction "VSS_2_35") (pintype "power_in"))
      (node (ref "STM1") (pin "47") (pinfunction "VSS_3_47") (pintype "power_in"))
      (node (ref "STM1") (pin "8") (pinfunction "VSSA_8") (pintype "power_in"))
      (node (ref "STM2") (pin "23") (pinfunction "VSS_23") (pintype "power_in"))
      (node (ref "STM2") (pin "35") (pinfunction "VSS_35") (pintype "power_in"))
      (node (ref "STM2") (pin "47") (pinfunction "VSS_47") (pintype "power_in"))
      (node (ref "STM2") (pin "8") (pinfunction "VSSA/VREF-_8") (pintype "power_in"))
      (node (ref "UESD1") (pin "2") (pinfunction "GND_2") (pintype "power_in"))
      (node (ref "USB*1") (pin "1") (pinfunction "GND_1") (pintype "power_in"))
      (node (ref "USB*1") (pin "12") (pinfunction "GND_12") (pintype "power_in"))
      (node (ref "USB*1") (pin "13") (pinfunction "SHEILD_13") (pintype "passive"))
      (node (ref "Y1") (pin "2") (pinfunction "GND_2") (pintype "passive"))
      (node (ref "Y1") (pin "4") (pinfunction "GND_4") (pintype "passive"))
      (node (ref "Y2") (pin "2") (pinfunction "GND_2") (pintype "passive"))
      (node (ref "Y2") (pin "4") (pinfunction "GND_4") (pintype "passive"))
    )
    (net (code "50") (name "Net-(C6-Pad2)") (class "Default")
      (node (ref "C6") (pin "2") (pinfunction "2_2") (pintype "passive"))
      (node (ref "R11") (pin "1") (pinfunction "1_1") (pintype "passive"))
      (node (ref "Y2") (pin "3") (pinfunction "3_3") (pintype "passive"))
    )
    (net (code "51") (name "Net-(D1-Pad2)") (class "Default")
      (node (ref "D1") (pin "2") (pinfunction "2_2") (pintype "passive"))
      (node (ref "R7") (pin "1") (pinfunction "1_1") (pintype "passive"))
    )
    (net (code "52") (name "Net-(D2-Pad2)") (class "Default")
      (node (ref "D2") (pin "2") (pinfunction "2_2") (pintype "passive"))
      (node (ref "R9") (pin "1") (pinfunction "1_1") (pintype "passive"))
    )
    (net (code "53") (name "Net-(D3-Pad1)") (class "Default")
      (node (ref "D3") (pin "1") (pinfunction "1_1") (pintype "passive"))
      (node (ref "R17") (pin "2") (pinfunction "2_2") (pintype "passive"))
    )
    (net (code "54") (name "Net-(D4-Pad2)") (class "Default")
      (node (ref "D4") (pin "2") (pinfunction "2_2") (pintype "passive"))
      (node (ref "R18") (pin "1") (pinfunction "1_1") (pintype "passive"))
    )
    (net (code "55") (name "Net-(D5-Pad2)") (class "Default")
      (node (ref "D5") (pin "2") (pinfunction "2_2") (pintype "passive"))
      (node (ref "R21") (pin "1") (pinfunction "1_1") (pintype "passive"))
    )
    (net (code "56") (name "Net-(D6-Pad2)") (class "Default")
      (node (ref "D6") (pin "2") (pinfunction "2_2") (pintype "passive"))
      (node (ref "R23") (pin "1") (pinfunction "1_1") (pintype "passive"))
    )
    (net (code "57") (name "Net-(Q1-B)") (class "Default")
      (node (ref "Q1") (pin "1") (pinfunction "B_1") (pintype "passive"))
      (node (ref "R14") (pin "1") (pinfunction "1_1") (pintype "passive"))
      (node (ref "R16") (pin "1") (pinfunction "1_1") (pintype "passive"))
      (node (ref "R19") (pin "2") (pinfunction "2_2") (pintype "passive"))
    )
    (net (code "58") (name "Net-(Q1-E)") (class "Default")
      (node (ref "Q1") (pin "2") (pinfunction "E_2") (pintype "passive"))
      (node (ref "R20") (pin "2") (pinfunction "2_2") (pintype "passive"))
    )
    (net (code "59") (name "Net-(STM1-BOOT0)") (class "Default")
      (node (ref "PP1") (pin "1") (pinfunction "1_1") (pintype "passive"))
      (node (ref "R4") (pin "2") (pinfunction "2_2") (pintype "passive"))
      (node (ref "STM1") (pin "44") (pinfunction "BOOT0_44") (pintype "bidirectional"))
    )
    (net (code "60") (name "Net-(STM1-NRST)") (class "Default")
      (node (ref "C1") (pin "2") (pinfunction "2_2") (pintype "passive"))
      (node (ref "R1") (pin "2") (pinfunction "2_2") (pintype "passive"))
      (node (ref "STM1") (pin "7") (pinfunction "NRST_7") (pintype "bidirectional"))
    )
    (net (code "61") (name "Net-(STM1-PA0-WKUP)") (class "Default")
      (node (ref "R5") (pin "1") (pinfunction "1_1") (pintype "passive"))
      (node (ref "R6") (pin "2") (pinfunction "2_2") (pintype "passive"))
      (node (ref "STM1") (pin "10") (pinfunction "PA0-WKUP_10") (pintype "bidirectional"))
    )
    (net (code "62") (name "Net-(STM1-PB12)") (class "Default")
      (node (ref "R10") (pin "1") (pinfunction "1_1") (pintype "passive"))
      (node (ref "STM1") (pin "25") (pinfunction "PB12_25") (pintype "bidirectional"))
    )
    (net (code "63") (name "Net-(STM1-PC13-TAMPER-RTC)") (class "Default")
      (node (ref "R2") (pin "2") (pinfunction "2_2") (pintype "passive"))
      (node (ref "STM1") (pin "2") (pinfunction "PC13-TAMPER-RTC_2") (pintype "bidirectional"))
    )
    (net (code "64") (name "Net-(STM1-PC14-OSC32_IN)") (class "Default")
      (node (ref "R3") (pin "2") (pinfunction "2_2") (pintype "passive"))
      (node (ref "STM1") (pin "3") (pinfunction "PC14-OSC32_IN_3") (pintype "bidirectional"))
    )
    (net (code "65") (name "Net-(STM1-PD0-OSC_IN)") (class "Default")
      (node (ref "C2") (pin "2") (pinfunction "2_2") (pintype "passive"))
      (node (ref "STM1") (pin "5") (pinfunction "PD0-OSC_IN_5") (pintype "bidirectional"))
      (node (ref "Y1") (pin "1") (pinfunction "1_1") (pintype "passive"))
    )
    (net (code "66") (name "Net-(STM1-PD1-OSC_OUT)") (class "Default")
      (node (ref "C3") (pin "2") (pinfunction "2_2") (pintype "passive"))
      (node (ref "STM1") (pin "6") (pinfunction "PD1-OSC_OUT_6") (pintype "bidirectional"))
      (node (ref "Y1") (pin "3") (pinfunction "3_3") (pintype "passive"))
    )
    (net (code "67") (name "Net-(STM2-BOOT0)") (class "Default")
      (node (ref "R12") (pin "2") (pinfunction "2_2") (pintype "passive"))
      (node (ref "STM2") (pin "44") (pinfunction "BOOT0_44") (pintype "input"))
    )
    (net (code "68") (name "Net-(STM2-VCAP1)") (class "Default")
      (node (ref "C7") (pin "1") (pinfunction "1_1") (pintype "passive"))
      (node (ref "STM2") (pin "22") (pinfunction "VCAP1_22") (pintype "power_in"))
    )
    (net (code "69") (name "Net-(USB*1-CC1)") (class "Default")
      (node (ref "R13") (pin "1") (pinfunction "1_1") (pintype "passive"))
      (node (ref "USB*1") (pin "4") (pinfunction "CC1_4") (pintype "output"))
    )
    (net (code "70") (name "Net-(USB*1-CC2)") (class "Default")
      (node (ref "R15") (pin "1") (pinfunction "1_1") (pintype "passive"))
      (node (ref "USB*1") (pin "10") (pinfunction "CC2_10") (pintype "output"))
    )
    (net (code "71") (name "VBUS") (class "Default")
      (node (ref "C21") (pin "1") (pinfunction "1_1") (pintype "passive"))
      (node (ref "CESD1") (pin "2") (pinfunction "2_2") (pintype "passive"))
      (node (ref "FB1") (pin "2") (pinfunction "2_2") (pintype "passive"))
      (node (ref "UESD1") (pin "5") (pinfunction "VBUS_5") (pintype "power_in"))
      (node (ref "USB*1") (pin "11") (pinfunction "VBUS_11") (pintype "power_in"))
      (node (ref "USB*1") (pin "2") (pinfunction "VBUS_2") (pintype "power_in"))
    )
    (net (code "72") (name "unconnected-(STM1-PA1-Pad11)") (class "Default")
      (node (ref "STM1") (pin "11") (pinfunction "PA1_11") (pintype "bidirectional+no_connect"))
    )
    (net (code "73") (name "unconnected-(STM1-PA2-Pad12)") (class "Default")
      (node (ref "STM1") (pin "12") (pinfunction "PA2_12") (pintype "bidirectional+no_connect"))
    )
    (net (code "74") (name "unconnected-(STM1-PA3-Pad13)") (class "Default")
      (node (ref "STM1") (pin "13") (pinfunction "PA3_13") (pintype "bidirectional+no_connect"))
    )
    (net (code "75") (name "unconnected-(STM1-PA4-Pad14)") (class "Default")
      (node (ref "STM1") (pin "14") (pinfunction "PA4_14") (pintype "bidirectional+no_connect"))
    )
    (net (code "76") (name "unconnected-(STM1-PA5-Pad15)") (class "Default")
      (node (ref "STM1") (pin "15") (pinfunction "PA5_15") (pintype "bidirectional+no_connect"))
    )
    (net (code "77") (name "unconnected-(STM1-PA6-Pad16)") (class "Default")
      (node (ref "STM1") (pin "16") (pinfunction "PA6_16") (pintype "bidirectional+no_connect"))
    )
    (net (code "78") (name "unconnected-(STM1-PA7-Pad17)") (class "Default")
      (node (ref "STM1") (pin "17") (pinfunction "PA7_17") (pintype "bidirectional+no_connect"))
    )
    (net (code "79") (name "unconnected-(STM1-PA8-Pad29)") (class "Default")
      (node (ref "STM1") (pin "29") (pinfunction "PA8_29") (pintype "bidirectional+no_connect"))
    )
    (net (code "80") (name "unconnected-(STM1-PB0-Pad18)") (class "Default")
      (node (ref "STM1") (pin "18") (pinfunction "PB0_18") (pintype "bidirectional+no_connect"))
    )
    (net (code "81") (name "unconnected-(STM1-PB1-Pad19)") (class "Default")
      (node (ref "STM1") (pin "19") (pinfunction "PB1_19") (pintype "bidirectional+no_connect"))
    )
    (net (code "82") (name "unconnected-(STM1-PB2-Pad20)") (class "Default")
      (node (ref "STM1") (pin "20") (pinfunction "PB2_20") (pintype "bidirectional+no_connect"))
    )
    (net (code "83") (name "unconnected-(STM1-PB3-Pad39)") (class "Default")
      (node (ref "STM1") (pin "39") (pinfunction "PB3_39") (pintype "bidirectional+no_connect"))
    )
    (net (code "84") (name "unconnected-(STM1-PB4-Pad40)") (class "Default")
      (node (ref "STM1") (pin "40") (pinfunction "PB4_40") (pintype "bidirectional+no_connect"))
    )
    (net (code "85") (name "unconnected-(STM1-PB5-Pad41)") (class "Default")
      (node (ref "STM1") (pin "41") (pinfunction "PB5_41") (pintype "bidirectional+no_connect"))
    )
    (net (code "86") (name "unconnected-(STM1-PB6-Pad42)") (class "Default")
      (node (ref "STM1") (pin "42") (pinfunction "PB6_42") (pintype "bidirectional+no_connect"))
    )
    (net (code "87") (name "unconnected-(STM1-PB7-Pad43)") (class "Default")
      (node (ref "STM1") (pin "43") (pinfunction "PB7_43") (pintype "bidirectional+no_connect"))
    )
    (net (code "88") (name "unconnected-(STM1-PB8-Pad45)") (class "Default")
      (node (ref "STM1") (pin "45") (pinfunction "PB8_45") (pintype "bidirectional+no_connect"))
    )
    (net (code "89") (name "unconnected-(STM1-PB9-Pad46)") (class "Default")
      (node (ref "STM1") (pin "46") (pinfunction "PB9_46") (pintype "bidirectional+no_connect"))
    )
    (net (code "90") (name "unconnected-(STM1-PB10-Pad21)") (class "Default")
      (node (ref "STM1") (pin "21") (pinfunction "PB10_21") (pintype "bidirectional+no_connect"))
    )
    (net (code "91") (name "unconnected-(STM1-PB11-Pad22)") (class "Default")
      (node (ref "STM1") (pin "22") (pinfunction "PB11_22") (pintype "bidirectional+no_connect"))
    )
    (net (code "92") (name "unconnected-(STM1-PB15-Pad28)") (class "Default")
      (node (ref "STM1") (pin "28") (pinfunction "PB15_28") (pintype "bidirectional+no_connect"))
    )
    (net (code "93") (name "unconnected-(STM1-PC15-OSC32_OUT-Pad4)") (class "Default")
      (node (ref "STM1") (pin "4") (pinfunction "PC15-OSC32_OUT_4") (pintype "bidirectional+no_connect"))
    )
    (net (code "94") (name "unconnected-(USB*1-SBU1-Pad9)") (class "Default")
      (node (ref "USB*1") (pin "9") (pinfunction "SBU1_9") (pintype "output+no_connect"))
    )
    (net (code "95") (name "unconnected-(USB*1-SBU2-Pad3)") (class "Default")
      (node (ref "USB*1") (pin "3") (pinfunction "SBU2_3") (pintype "output+no_connect"))
    )
  )
)
